# diagrama-esquematico-r00.net
KiCad netlist of a schematic drawn in EAGLE
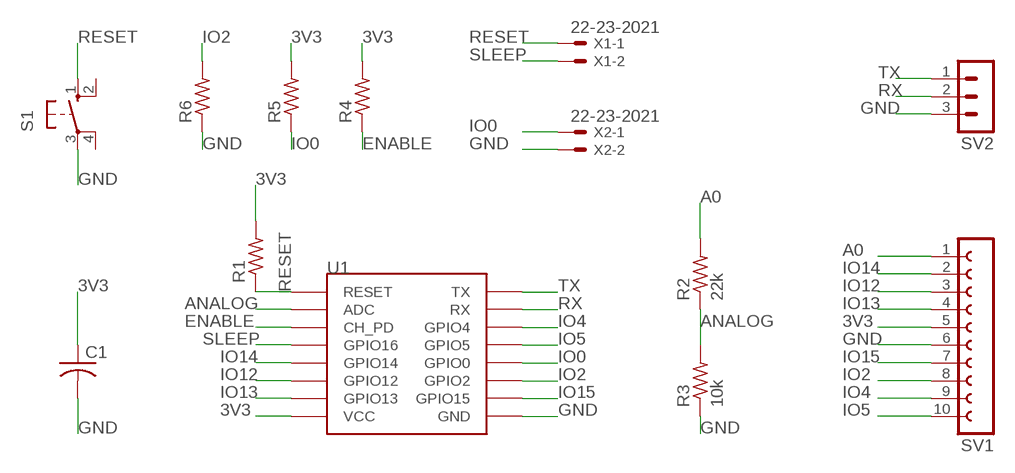
[diagram p0: schematic, sheet 1]

(export (version "E")
  (design (tool "Eeschema 10.0.6"))
  (components
    (comp (ref "C1")
      (value "C-US025-030X050")
      (footprint "eagle-import:C025-030X050")
      (libsource (lib "eagle-import") (part "C-US025-030X050"))
    )
    (comp (ref "R1")
      (value "R-US_0207/10")
      (footprint "eagle-import:0207_10")
      (libsource (lib "eagle-import") (part "R-US_0207/10"))
    )
    (comp (ref "R2")
      (value "22k")
      (footprint "eagle-import:0207_10")
      (libsource (lib "eagle-import") (part "R-US_0207/10"))
    )
    (comp (ref "R3")
      (value "10k")
      (footprint "eagle-import:0207_10")
      (libsource (lib "eagle-import") (part "R-US_0207/10"))
    )
    (comp (ref "R4")
      (value "R-US_0207/10")
      (footprint "eagle-import:0207_10")
      (libsource (lib "eagle-import") (part "R-US_0207/10"))
    )
    (comp (ref "R5")
      (value "R-US_0207/10")
      (footprint "eagle-import:0207_10")
      (libsource (lib "eagle-import") (part "R-US_0207/10"))
    )
    (comp (ref "R6")
      (value "R-US_0207/10")
      (footprint "eagle-import:0207_10")
      (libsource (lib "eagle-import") (part "R-US_0207/10"))
    )
    (comp (ref "S1")
      (value "10-XX")
      (footprint "eagle-import:B3F-10XX")
      (fields (field (name "MPN") "B3F-1000"))
      (libsource (lib "eagle-import") (part "10-XX"))
    )
    (comp (ref "SV1")
      (value "FE10-1")
      (footprint "eagle-import:FE10")
      (libsource (lib "eagle-import") (part "FE10-1"))
    )
    (comp (ref "SV2")
      (value "MA03-1")
      (footprint "eagle-import:MA03-1")
      (libsource (lib "eagle-import") (part "MA03-1"))
    )
    (comp (ref "U1")
      (value "ESP12")
      (footprint "eagle-import:ESP12")
      (libsource (lib "eagle-import") (part "ESP12"))
    )
    (comp (ref "X1")
      (value "22-23-2021")
      (footprint "eagle-import:22-23-2021")
      (fields (field (name "MF") "MOLEX"))
      (libsource (lib "eagle-import") (part "22-23-2021"))
    )
    (comp (ref "X2")
      (value "22-23-2021")
      (footprint "eagle-import:22-23-2021")
      (fields (field (name "MF") "MOLEX"))
      (libsource (lib "eagle-import") (part "22-23-2021"))
    )
  )
  (nets
    (net (code "1") (name "/3V3") (class "Default")
      (node (ref "C1") (pin "1") (pinfunction "1_1") (pintype "passive"))
      (node (ref "R1") (pin "2") (pinfunction "2_2") (pintype "passive"))
      (node (ref "R4") (pin "2") (pinfunction "2_2") (pintype "passive"))
      (node (ref "R5") (pin "2") (pinfunction "2_2") (pintype "passive"))
      (node (ref "SV1") (pin "5") (pinfunction "5_5") (pintype "passive"))
      (node (ref "U1") (pin "VCC") (pinfunction "VCC_VCC") (pintype "bidirectional"))
    )
    (net (code "2") (name "/A0") (class "Default")
      (node (ref "R2") (pin "2") (pinfunction "2_2") (pintype "passive"))
      (node (ref "SV1") (pin "1") (pinfunction "1_1") (pintype "passive"))
    )
    (net (code "3") (name "/ANALOG") (class "Default")
      (node (ref "R2") (pin "1") (pinfunction "1_1") (pintype "passive"))
      (node (ref "R3") (pin "2") (pinfunction "2_2") (pintype "passive"))
      (node (ref "U1") (pin "ADC") (pinfunction "ADC_ADC") (pintype "bidirectional"))
    )
    (net (code "4") (name "/ENABLE") (class "Default")
      (node (ref "R4") (pin "1") (pinfunction "1_1") (pintype "passive"))
      (node (ref "U1") (pin "CH_PD") (pinfunction "CH_PD_CH_PD") (pintype "bidirectional"))
    )
    (net (code "5") (name "/GND") (class "Default")
      (node (ref "C1") (pin "2") (pinfunction "2_2") (pintype "passive"))
      (node (ref "R3") (pin "1") (pinfunction "1_1") (pintype "passive"))
      (node (ref "R6") (pin "1") (pinfunction "1_1") (pintype "passive"))
      (node (ref "S1") (pin "3") (pinfunction "P_3") (pintype "passive"))
      (node (ref "SV1") (pin "6") (pinfunction "6_6") (pintype "passive"))
      (node (ref "SV2") (pin "3") (pinfunction "3_3") (pintype "passive"))
      (node (ref "U1") (pin "GND") (pinfunction "GND_GND") (pintype "bidirectional"))
      (node (ref "X2") (pin "2") (pinfunction "S_2") (pintype "passive"))
    )
    (net (code "6") (name "/IO0") (class "Default")
      (node (ref "R5") (pin "1") (pinfunction "1_1") (pintype "passive"))
      (node (ref "U1") (pin "GPIO0") (pinfunction "GPIO0_GPIO0") (pintype "bidirectional"))
      (node (ref "X2") (pin "1") (pinfunction "S_1") (pintype "passive"))
    )
    (net (code "7") (name "/IO2") (class "Default")
      (node (ref "R6") (pin "2") (pinfunction "2_2") (pintype "passive"))
      (node (ref "SV1") (pin "8") (pinfunction "8_8") (pintype "passive"))
      (node (ref "U1") (pin "GPIO2") (pinfunction "GPIO2_GPIO2") (pintype "bidirectional"))
    )
    (net (code "8") (name "/IO4") (class "Default")
      (node (ref "SV1") (pin "9") (pinfunction "9_9") (pintype "passive"))
      (node (ref "U1") (pin "GPIO4") (pinfunction "GPIO4_GPIO4") (pintype "bidirectional"))
    )
    (net (code "9") (name "/IO5") (class "Default")
      (node (ref "SV1") (pin "10") (pinfunction "10_10") (pintype "passive"))
      (node (ref "U1") (pin "GPIO5") (pinfunction "GPIO5_GPIO5") (pintype "bidirectional"))
    )
    (net (code "10") (name "/IO12") (class "Default")
      (node (ref "SV1") (pin "3") (pinfunction "3_3") (pintype "passive"))
      (node (ref "U1") (pin "GPIO12") (pinfunction "GPIO12_GPIO12") (pintype "bidirectional"))
    )
    (net (code "11") (name "/IO13") (class "Default")
      (node (ref "SV1") (pin "4") (pinfunction "4_4") (pintype "passive"))
      (node (ref "U1") (pin "GPIO13") (pinfunction "GPIO13_GPIO13") (pintype "bidirectional"))
    )
    (net (code "12") (name "/IO14") (class "Default")
      (node (ref "SV1") (pin "2") (pinfunction "2_2") (pintype "passive"))
      (node (ref "U1") (pin "GPIO14") (pinfunction "GPIO14_GPIO14") (pintype "bidirectional"))
    )
    (net (code "13") (name "/IO15") (class "Default")
      (node (ref "SV1") (pin "7") (pinfunction "7_7") (pintype "passive"))
      (node (ref "U1") (pin "GPIO15") (pinfunction "GPIO15_GPIO15") (pintype "bidirectional"))
    )
    (net (code "14") (name "/RESET") (class "Default")
      (node (ref "R1") (pin "1") (pinfunction "1_1") (pintype "passive"))
      (node (ref "S1") (pin "1") (pinfunction "S_1") (pintype "passive"))
      (node (ref "U1") (pin "RESET") (pinfunction "RESET_RESET") (pintype "bidirectional"))
      (node (ref "X1") (pin "1") (pinfunction "S_1") (pintype "passive"))
    )
    (net (code "15") (name "/RX") (class "Default")
      (node (ref "SV2") (pin "2") (pinfunction "2_2") (pintype "passive"))
      (node (ref "U1") (pin "RX") (pinfunction "RX_RX") (pintype "bidirectional"))
    )
    (net (code "16") (name "/SLEEP") (class "Default")
      (node (ref "U1") (pin "GPIO16") (pinfunction "GPIO16_GPIO16") (pintype "bidirectional"))
      (node (ref "X1") (pin "2") (pinfunction "S_2") (pintype "passive"))
    )
    (net (code "17") (name "/TX") (class "Default")
      (node (ref "SV2") (pin "1") (pinfunction "1_1") (pintype "passive"))
      (node (ref "U1") (pin "TX") (pinfunction "TX_TX") (pintype "bidirectional"))
    )
    (net (code "18") (name "unconnected-(S1-P1-Pad4)") (class "Default")
      (node (ref "S1") (pin "4") (pinfunction "P1_4") (pintype "passive"))
    )
    (net (code "19") (name "unconnected-(S1-S1-Pad2)") (class "Default")
      (node (ref "S1") (pin "2") (pinfunction "S1_2") (pintype "passive"))
    )
  )
)
